# edp_to_DP.net
KiCad netlist of a schematic drawn in EAGLE
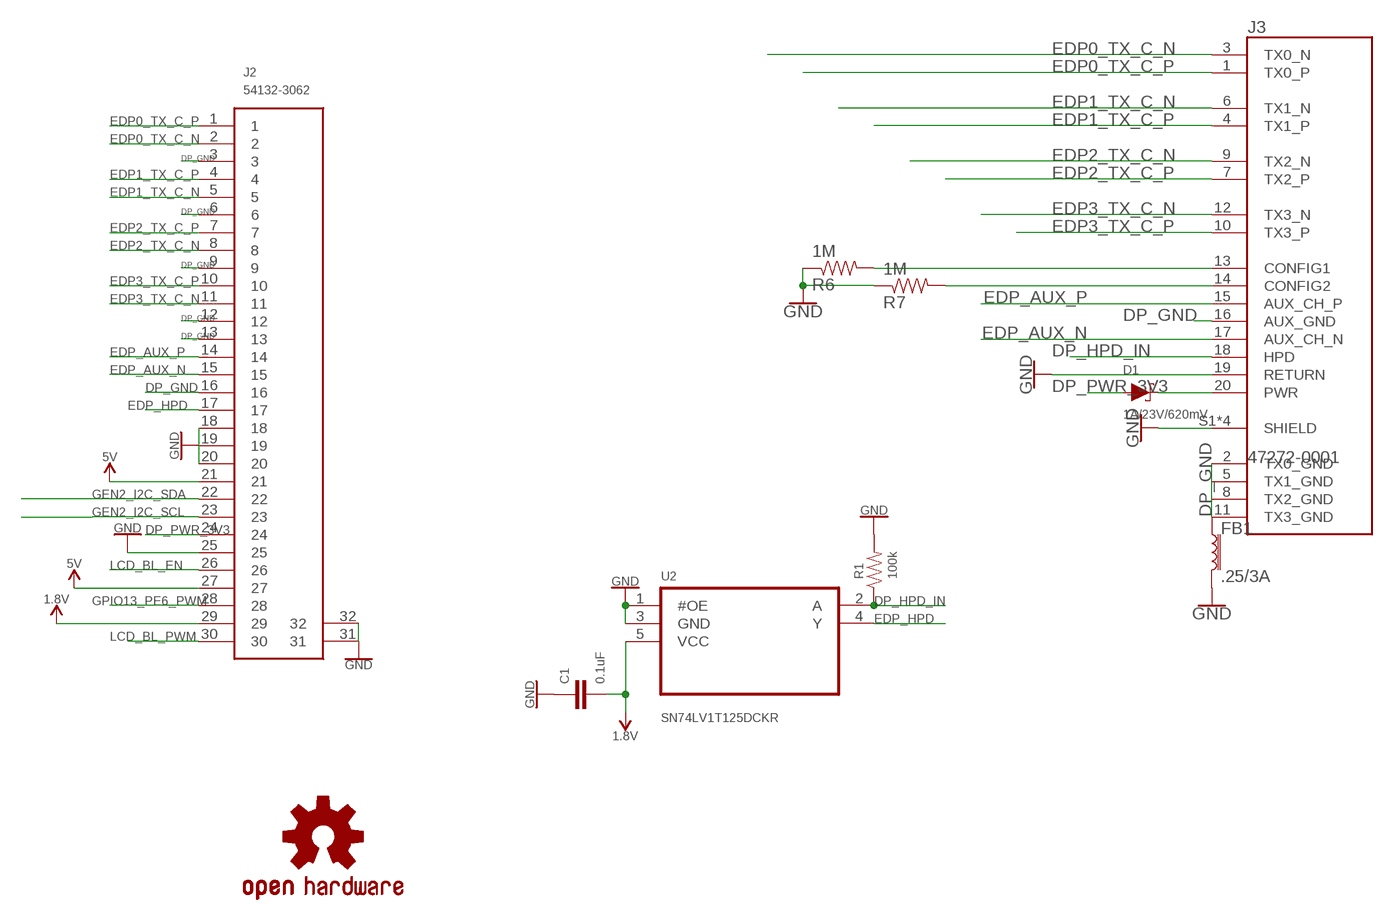
[diagram p0: schematic, sheet 1]

(export (version "E")
  (design (tool "Eeschema 10.0.6"))
  (components
    (comp (ref "C1")
      (value "0.1uF")
      (footprint "eagle-import:0603")
      (libsource (lib "eagle-import") (part "10NF-0603-50V-10%"))
    )
    (comp (ref "D1")
      (value "1A/23V/620mV")
      (footprint "eagle-import:SOD-323")
      (libsource (lib "eagle-import") (part "DIODE-SCHOTTKY-BAT20J"))
    )
    (comp (ref "FB1")
      (value ".25/3A")
      (footprint "eagle-import:0603")
      (libsource (lib "eagle-import") (part "FERRITE_BEAD-0603"))
    )
    (comp (ref "J2")
      (value "54132-3062")
      (footprint "eagle-import:54132-3062")
      (fields (field (name "MOUSER_PART_NUMBER") "538-54132-3062"))
      (libsource (lib "eagle-import") (part "54132-3062"))
    )
    (comp (ref "J3")
      (value "47272-0001")
      (footprint "eagle-import:MOLEX_47272-0001")
      (fields (field (name "MF") "Molex"))
      (libsource (lib "eagle-import") (part "47272-0001"))
    )
    (comp (ref "LOGO1")
      (value "OSHW-LOGOS-COPPER")
      (footprint "eagle-import:OSHW-LOGO-S_COPPER")
      (libsource (lib "eagle-import") (part "OSHW-LOGOS-COPPER"))
    )
    (comp (ref "R1")
      (value "100k")
      (footprint "eagle-import:0805")
      (libsource (lib "eagle-import") (part "RESISTOR0805-RES"))
    )
    (comp (ref "R6")
      (value "1M")
      (footprint "eagle-import:0805")
      (libsource (lib "eagle-import") (part "RESISTOR0805-RES"))
    )
    (comp (ref "R7")
      (value "1M")
      (footprint "eagle-import:0805")
      (libsource (lib "eagle-import") (part "RESISTOR0805-RES"))
    )
    (comp (ref "U2")
      (value "SN74LV1T125DCKR")
      (footprint "eagle-import:SOT65P210X110-5N")
      (fields (field (name "MF") "Texas Instruments"))
      (libsource (lib "eagle-import") (part "SN74LV1T125DCKR"))
    )
  )
  (nets
    (net (code "1") (name "/DP_GND") (class "Default")
      (node (ref "FB1") (pin "1") (pinfunction "1_1") (pintype "passive"))
      (node (ref "J2") (pin "12") (pinfunction "12_12") (pintype "bidirectional"))
      (node (ref "J2") (pin "13") (pinfunction "13_13") (pintype "bidirectional"))
      (node (ref "J2") (pin "16") (pinfunction "16_16") (pintype "bidirectional"))
      (node (ref "J2") (pin "3") (pinfunction "3_3") (pintype "bidirectional"))
      (node (ref "J2") (pin "6") (pinfunction "6_6") (pintype "bidirectional"))
      (node (ref "J2") (pin "9") (pinfunction "9_9") (pintype "bidirectional"))
      (node (ref "J3") (pin "11") (pinfunction "TX3_GND_11") (pintype "passive"))
      (node (ref "J3") (pin "16") (pinfunction "AUX_GND_16") (pintype "passive"))
      (node (ref "J3") (pin "2") (pinfunction "TX0_GND_2") (pintype "passive"))
      (node (ref "J3") (pin "5") (pinfunction "TX1_GND_5") (pintype "passive"))
      (node (ref "J3") (pin "8") (pinfunction "TX2_GND_8") (pintype "passive"))
    )
    (net (code "2") (name "/DP_HPD_IN") (class "Default")
      (node (ref "J3") (pin "18") (pinfunction "HPD_18") (pintype "passive"))
      (node (ref "R1") (pin "1") (pinfunction "1_1") (pintype "passive"))
      (node (ref "U2") (pin "2") (pinfunction "A_2") (pintype "output"))
    )
    (net (code "3") (name "/DP_PWR_3V3") (class "Default")
      (node (ref "D1") (pin "A") (pinfunction "A_A") (pintype "passive"))
      (node (ref "J2") (pin "24") (pinfunction "24_24") (pintype "bidirectional"))
    )
    (net (code "4") (name "/EDP0_TX_C_N") (class "Default")
      (node (ref "J2") (pin "2") (pinfunction "2_2") (pintype "bidirectional"))
      (node (ref "J3") (pin "3") (pinfunction "TX0_N_3") (pintype "passive"))
    )
    (net (code "5") (name "/EDP0_TX_C_P") (class "Default")
      (node (ref "J2") (pin "1") (pinfunction "1_1") (pintype "bidirectional"))
      (node (ref "J3") (pin "1") (pinfunction "TX0_P_1") (pintype "passive"))
    )
    (net (code "6") (name "/EDP1_TX_C_N") (class "Default")
      (node (ref "J2") (pin "5") (pinfunction "5_5") (pintype "bidirectional"))
      (node (ref "J3") (pin "6") (pinfunction "TX1_N_6") (pintype "passive"))
    )
    (net (code "7") (name "/EDP1_TX_C_P") (class "Default")
      (node (ref "J2") (pin "4") (pinfunction "4_4") (pintype "bidirectional"))
      (node (ref "J3") (pin "4") (pinfunction "TX1_P_4") (pintype "passive"))
    )
    (net (code "8") (name "/EDP2_TX_C_N") (class "Default")
      (node (ref "J2") (pin "8") (pinfunction "8_8") (pintype "bidirectional"))
      (node (ref "J3") (pin "9") (pinfunction "TX2_N_9") (pintype "passive"))
    )
    (net (code "9") (name "/EDP2_TX_C_P") (class "Default")
      (node (ref "J2") (pin "7") (pinfunction "7_7") (pintype "bidirectional"))
      (node (ref "J3") (pin "7") (pinfunction "TX2_P_7") (pintype "passive"))
    )
    (net (code "10") (name "/EDP3_TX_C_N") (class "Default")
      (node (ref "J2") (pin "11") (pinfunction "11_11") (pintype "bidirectional"))
      (node (ref "J3") (pin "12") (pinfunction "TX3_N_12") (pintype "passive"))
    )
    (net (code "11") (name "/EDP3_TX_C_P") (class "Default")
      (node (ref "J2") (pin "10") (pinfunction "10_10") (pintype "bidirectional"))
      (node (ref "J3") (pin "10") (pinfunction "TX3_P_10") (pintype "passive"))
    )
    (net (code "12") (name "/EDP_AUX_N") (class "Default")
      (node (ref "J2") (pin "15") (pinfunction "15_15") (pintype "bidirectional"))
      (node (ref "J3") (pin "17") (pinfunction "AUX_CH_N_17") (pintype "passive"))
    )
    (net (code "13") (name "/EDP_AUX_P") (class "Default")
      (node (ref "J2") (pin "14") (pinfunction "14_14") (pintype "bidirectional"))
      (node (ref "J3") (pin "15") (pinfunction "AUX_CH_P_15") (pintype "passive"))
    )
    (net (code "14") (name "/EDP_HPD") (class "Default")
      (node (ref "J2") (pin "17") (pinfunction "17_17") (pintype "bidirectional"))
      (node (ref "U2") (pin "4") (pinfunction "Y_4") (pintype "output"))
    )
    (net (code "15") (name "/GEN2_I2C_SCL") (class "Default")
      (node (ref "J2") (pin "23") (pinfunction "23_23") (pintype "bidirectional"))
    )
    (net (code "16") (name "/GEN2_I2C_SDA") (class "Default")
      (node (ref "J2") (pin "22") (pinfunction "22_22") (pintype "bidirectional"))
    )
    (net (code "17") (name "/GPIO13_PE6_PWM") (class "Default")
      (node (ref "J2") (pin "28") (pinfunction "28_28") (pintype "bidirectional"))
    )
    (net (code "18") (name "/LCD_BL_EN") (class "Default")
      (node (ref "J2") (pin "26") (pinfunction "26_26") (pintype "bidirectional"))
    )
    (net (code "19") (name "/LCD_BL_PWM") (class "Default")
      (node (ref "J2") (pin "30") (pinfunction "30_30") (pintype "bidirectional"))
    )
    (net (code "20") (name "1.8V") (class "Default")
      (node (ref "C1") (pin "2") (pinfunction "2_2") (pintype "passive"))
      (node (ref "J2") (pin "29") (pinfunction "29_29") (pintype "bidirectional"))
      (node (ref "U2") (pin "5") (pinfunction "VCC_5") (pintype "input"))
    )
    (net (code "21") (name "5V") (class "Default")
      (node (ref "J2") (pin "21") (pinfunction "21_21") (pintype "bidirectional"))
      (node (ref "J2") (pin "27") (pinfunction "27_27") (pintype "bidirectional"))
    )
    (net (code "22") (name "GND") (class "Default")
      (node (ref "C1") (pin "1") (pinfunction "1_1") (pintype "passive"))
      (node (ref "FB1") (pin "2") (pinfunction "2_2") (pintype "passive"))
      (node (ref "J2") (pin "18") (pinfunction "18_18") (pintype "bidirectional"))
      (node (ref "J2") (pin "19") (pinfunction "19_19") (pintype "bidirectional"))
      (node (ref "J2") (pin "20") (pinfunction "20_20") (pintype "bidirectional"))
      (node (ref "J2") (pin "25") (pinfunction "25_25") (pintype "bidirectional"))
      (node (ref "J2") (pin "31") (pinfunction "31_31") (pintype "bidirectional"))
      (node (ref "J2") (pin "32") (pinfunction "32_32") (pintype "bidirectional"))
      (node (ref "J3") (pin "19") (pinfunction "RETURN_19") (pintype "passive"))
      (node (ref "J3") (pin "S1") (pinfunction "SHIELD_S1") (pintype "passive"))
      (node (ref "J3") (pin "S2") (pinfunction "SHIELD_S2") (pintype "passive"))
      (node (ref "J3") (pin "S3") (pinfunction "SHIELD_S3") (pintype "passive"))
      (node (ref "J3") (pin "S4") (pinfunction "SHIELD_S4") (pintype "passive"))
      (node (ref "R1") (pin "2") (pinfunction "2_2") (pintype "passive"))
      (node (ref "R6") (pin "1") (pinfunction "1_1") (pintype "passive"))
      (node (ref "R7") (pin "1") (pinfunction "1_1") (pintype "passive"))
      (node (ref "U2") (pin "1") (pinfunction "#OE_1") (pintype "input"))
      (node (ref "U2") (pin "3") (pinfunction "GND_3") (pintype "input"))
    )
    (net (code "23") (name "Net-(J3-CONFIG1)") (class "Default")
      (node (ref "J3") (pin "13") (pinfunction "CONFIG1_13") (pintype "passive"))
      (node (ref "R6") (pin "2") (pinfunction "2_2") (pintype "passive"))
    )
    (net (code "24") (name "Net-(J3-CONFIG2)") (class "Default")
      (node (ref "J3") (pin "14") (pinfunction "CONFIG2_14") (pintype "passive"))
      (node (ref "R7") (pin "2") (pinfunction "2_2") (pintype "passive"))
    )
    (net (code "25") (name "Net-(J3-PWR)") (class "Default")
      (node (ref "D1") (pin "C") (pinfunction "C_C") (pintype "passive"))
      (node (ref "J3") (pin "20") (pinfunction "PWR_20") (pintype "passive"))
    )
  )
)
